# 1btn_v1.net
KiCad netlist of a schematic drawn in EAGLE
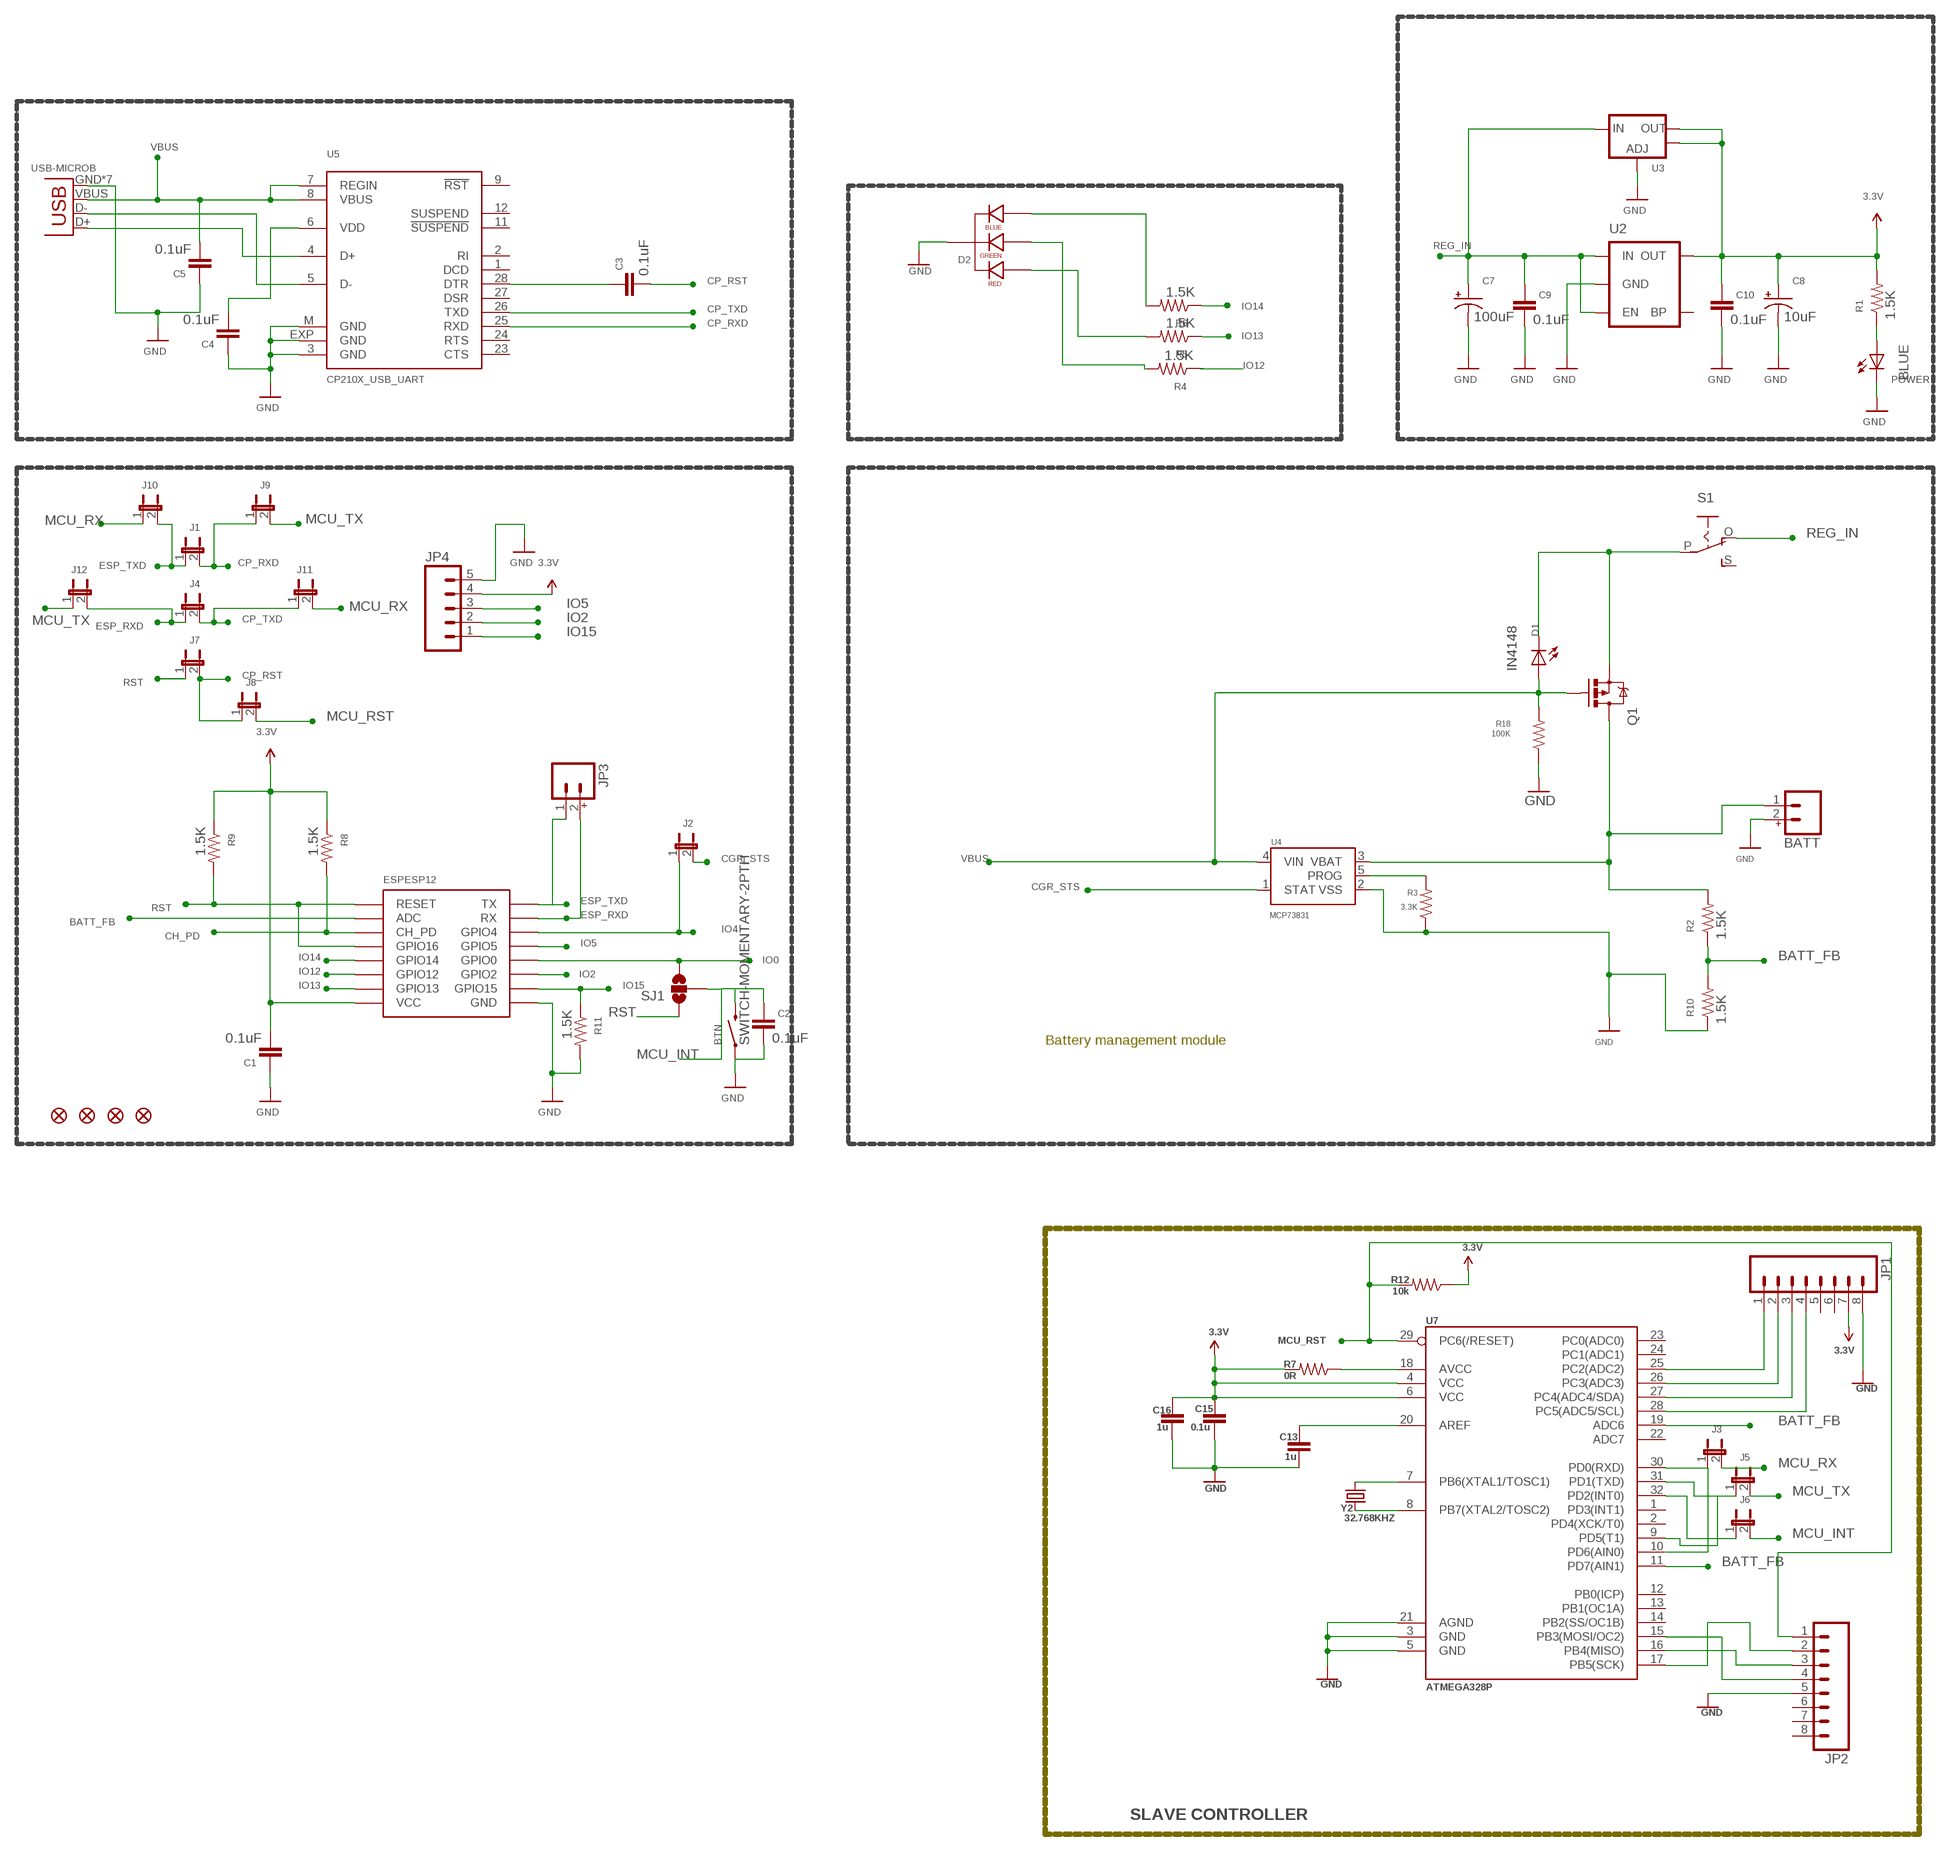
[diagram p0: schematic, sheet 1]

(export (version "E")
  (design (tool "Eeschema 10.0.6"))
  (components
    (comp (ref "BATT")
      (value "M02JST-PTH-2")
      (footprint "eagle-import:JST-2-PTH")
      (libsource (lib "eagle-import") (part "M02JST-PTH-2"))
    )
    (comp (ref "BTN")
      (value "SWITCH-MOMENTARY-2PTH")
      (footprint "eagle-import:TACTILE-PTH")
      (libsource (lib "eagle-import") (part "SWITCH-MOMENTARY-2PTH"))
    )
    (comp (ref "C1")
      (value "0.1uF")
      (footprint "eagle-import:0805")
      (libsource (lib "eagle-import") (part "SparkFun-Passives_CAP0805"))
    )
    (comp (ref "C2")
      (value "0.1uF")
      (footprint "eagle-import:0805")
      (libsource (lib "eagle-import") (part "SparkFun-Passives_CAP0805"))
    )
    (comp (ref "C3")
      (value "0.1uF")
      (footprint "eagle-import:0805")
      (libsource (lib "eagle-import") (part "SparkFun-Passives_CAP0805"))
    )
    (comp (ref "C4")
      (value "0.1uF")
      (footprint "eagle-import:0805")
      (libsource (lib "eagle-import") (part "SparkFun-Passives_CAP0805"))
    )
    (comp (ref "C5")
      (value "0.1uF")
      (footprint "eagle-import:0805")
      (libsource (lib "eagle-import") (part "SparkFun-Passives_CAP0805"))
    )
    (comp (ref "C7")
      (value "100uF")
      (footprint "eagle-import:EIA3216-KIT")
      (libsource (lib "eagle-import") (part "CAP_POL1206-KIT"))
    )
    (comp (ref "C8")
      (value "10uF")
      (footprint "eagle-import:EIA3216-KIT")
      (libsource (lib "eagle-import") (part "CAP_POL1206-KIT"))
    )
    (comp (ref "C9")
      (value "0.1uF")
      (footprint "eagle-import:0805")
      (libsource (lib "eagle-import") (part "SparkFun-Passives_CAP0805"))
    )
    (comp (ref "C10")
      (value "0.1uF")
      (footprint "eagle-import:0805")
      (libsource (lib "eagle-import") (part "SparkFun-Passives_CAP0805"))
    )
    (comp (ref "C13")
      (value "1u")
      (footprint "eagle-import:0805")
      (libsource (lib "eagle-import") (part "CAP0805"))
    )
    (comp (ref "C15")
      (value "0.1u")
      (footprint "eagle-import:0805")
      (libsource (lib "eagle-import") (part "CAP0805"))
    )
    (comp (ref "C16")
      (value "1u")
      (footprint "eagle-import:0805")
      (libsource (lib "eagle-import") (part "CAP0805"))
    )
    (comp (ref "D1")
      (value "IN4148")
      (footprint "eagle-import:LED-1206")
      (libsource (lib "eagle-import") (part "LED1206"))
    )
    (comp (ref "D2")
      (value "LED-RGB-CC-THRUCLEAR")
      (footprint "eagle-import:LED-RGB-THRU")
      (libsource (lib "eagle-import") (part "LED-RGB-CC-THRUCLEAR"))
    )
    (comp (ref "ESP")
      (value "ESP12")
      (footprint "eagle-import:ESP12")
      (libsource (lib "eagle-import") (part "ESP12"))
    )
    (comp (ref "FID1")
      (value "FIDUCIAL1X2")
      (footprint "eagle-import:FIDUCIAL-1X2")
      (libsource (lib "eagle-import") (part "FIDUCIAL1X2"))
    )
    (comp (ref "FID2")
      (value "FIDUCIAL1X2")
      (footprint "eagle-import:FIDUCIAL-1X2")
      (libsource (lib "eagle-import") (part "FIDUCIAL1X2"))
    )
    (comp (ref "FID3")
      (value "FIDUCIAL1X2")
      (footprint "eagle-import:FIDUCIAL-1X2")
      (libsource (lib "eagle-import") (part "FIDUCIAL1X2"))
    )
    (comp (ref "FID4")
      (value "FIDUCIAL1X2")
      (footprint "eagle-import:FIDUCIAL-1X2")
      (libsource (lib "eagle-import") (part "FIDUCIAL1X2"))
    )
    (comp (ref "J1")
      (value "JUMPER-2SMD-NC")
      (footprint "eagle-import:SJ_2S")
      (libsource (lib "eagle-import") (part "JUMPER-2SMD-NC"))
    )
    (comp (ref "J2")
      (value "JUMPER-2SMD-NC")
      (footprint "eagle-import:SJ_2S")
      (libsource (lib "eagle-import") (part "JUMPER-2SMD-NC"))
    )
    (comp (ref "J3")
      (value "JUMPER-2SMD-NC")
      (footprint "eagle-import:SJ_2S")
      (libsource (lib "eagle-import") (part "JUMPER-2SMD-NC"))
    )
    (comp (ref "J4")
      (value "JUMPER-2SMD-NC")
      (footprint "eagle-import:SJ_2S")
      (libsource (lib "eagle-import") (part "JUMPER-2SMD-NC"))
    )
    (comp (ref "J5")
      (value "JUMPER-2SMD-NC")
      (footprint "eagle-import:SJ_2S")
      (libsource (lib "eagle-import") (part "JUMPER-2SMD-NC"))
    )
    (comp (ref "J6")
      (value "JUMPER-2SMD-NC")
      (footprint "eagle-import:SJ_2S")
      (libsource (lib "eagle-import") (part "JUMPER-2SMD-NC"))
    )
    (comp (ref "J7")
      (value "JUMPER-2SMD-NC")
      (footprint "eagle-import:SJ_2S")
      (libsource (lib "eagle-import") (part "JUMPER-2SMD-NC"))
    )
    (comp (ref "J8")
      (value "JUMPER-2SMD-NC")
      (footprint "eagle-import:SJ_2S")
      (libsource (lib "eagle-import") (part "JUMPER-2SMD-NC"))
    )
    (comp (ref "J9")
      (value "JUMPER-2SMD-NC")
      (footprint "eagle-import:SJ_2S")
      (libsource (lib "eagle-import") (part "JUMPER-2SMD-NC"))
    )
    (comp (ref "J10")
      (value "JUMPER-2SMD-NC")
      (footprint "eagle-import:SJ_2S")
      (libsource (lib "eagle-import") (part "JUMPER-2SMD-NC"))
    )
    (comp (ref "J11")
      (value "JUMPER-2SMD-NC")
      (footprint "eagle-import:SJ_2S")
      (libsource (lib "eagle-import") (part "JUMPER-2SMD-NC"))
    )
    (comp (ref "J12")
      (value "JUMPER-2SMD-NC")
      (footprint "eagle-import:SJ_2S")
      (libsource (lib "eagle-import") (part "JUMPER-2SMD-NC"))
    )
    (comp (ref "JP1")
      (value "M08NO_SILK")
      (footprint "eagle-import:1X08_PIN1_NO_SILK")
      (libsource (lib "eagle-import") (part "M08NO_SILK"))
    )
    (comp (ref "JP2")
      (value "M08NO_SILK")
      (footprint "eagle-import:1X08_PIN1_NO_SILK")
      (libsource (lib "eagle-import") (part "M08NO_SILK"))
    )
    (comp (ref "JP3")
      (value "M02PTH")
      (footprint "eagle-import:1X02")
      (libsource (lib "eagle-import") (part "M02PTH"))
    )
    (comp (ref "JP4")
      (value "M05PTH")
      (footprint "eagle-import:1X05")
      (libsource (lib "eagle-import") (part "M05PTH"))
    )
    (comp (ref "POWER")
      (value "BLUE")
      (footprint "eagle-import:LED-0805")
      (libsource (lib "eagle-import") (part "LED"))
    )
    (comp (ref "Q1")
      (value "MOSFET-PCHANNELSMD")
      (footprint "eagle-import:SOT23-3")
      (libsource (lib "eagle-import") (part "MOSFET-PCHANNELSMD"))
    )
    (comp (ref "R1")
      (value "1.5K")
      (footprint "eagle-import:0805")
      (libsource (lib "eagle-import") (part "RESISTOR0805-RES"))
    )
    (comp (ref "R2")
      (value "1.5K")
      (footprint "eagle-import:0805")
      (libsource (lib "eagle-import") (part "RESISTOR0805-RES"))
    )
    (comp (ref "R3")
      (value "3.3K")
      (footprint "eagle-import:0805")
      (libsource (lib "eagle-import") (part "RESISTOR0805-RES"))
    )
    (comp (ref "R4")
      (value "1.5K")
      (footprint "eagle-import:0805")
      (libsource (lib "eagle-import") (part "RESISTOR0805-RES"))
    )
    (comp (ref "R5")
      (value "1.5K")
      (footprint "eagle-import:0805")
      (libsource (lib "eagle-import") (part "RESISTOR0805-RES"))
    )
    (comp (ref "R6")
      (value "1.5K")
      (footprint "eagle-import:0805")
      (libsource (lib "eagle-import") (part "RESISTOR0805-RES"))
    )
    (comp (ref "R7")
      (value "0R")
      (footprint "eagle-import:0805")
      (libsource (lib "eagle-import") (part "RESISTOR0805-RES"))
    )
    (comp (ref "R8")
      (value "1.5K")
      (footprint "eagle-import:0805")
      (libsource (lib "eagle-import") (part "RESISTOR0805-RES"))
    )
    (comp (ref "R9")
      (value "1.5K")
      (footprint "eagle-import:0805")
      (libsource (lib "eagle-import") (part "RESISTOR0805-RES"))
    )
    (comp (ref "R10")
      (value "1.5K")
      (footprint "eagle-import:0805")
      (libsource (lib "eagle-import") (part "RESISTOR0805-RES"))
    )
    (comp (ref "R11")
      (value "1.5K")
      (footprint "eagle-import:0805")
      (libsource (lib "eagle-import") (part "RESISTOR0805-RES"))
    )
    (comp (ref "R12")
      (value "10k")
      (footprint "eagle-import:0805")
      (libsource (lib "eagle-import") (part "RESISTOR0805-RES"))
    )
    (comp (ref "R18")
      (value "100K")
      (footprint "eagle-import:0805")
      (libsource (lib "eagle-import") (part "RESISTOR0805-RES"))
    )
    (comp (ref "S1")
      (value "EG1218S")
      (footprint "eagle-import:EG1218")
      (libsource (lib "eagle-import") (part "EG1218S"))
    )
    (comp (ref "SJ1")
      (value "SOLDERJUMPER_2WAYS")
      (footprint "eagle-import:SJ_3")
      (libsource (lib "eagle-import") (part "SOLDERJUMPER_2WAYS"))
    )
    (comp (ref "U2")
      (value "MIC52053.3V")
      (footprint "eagle-import:SOT23-5")
      (libsource (lib "eagle-import") (part "MIC52053.3V"))
    )
    (comp (ref "U3")
      (value "V_REG_LM1117SOT223")
      (footprint "eagle-import:SOT223")
      (libsource (lib "eagle-import") (part "V_REG_LM1117SOT223"))
    )
    (comp (ref "U4")
      (value "MCP73831")
      (footprint "eagle-import:SOT23-5")
      (libsource (lib "eagle-import") (part "MCP73831"))
    )
    (comp (ref "U5")
      (value "CP210X_USB_UART")
      (footprint "eagle-import:MLP28")
      (libsource (lib "eagle-import") (part "CP210X_USB_UART"))
    )
    (comp (ref "U7")
      (value "ATMEGA328P")
      (footprint "eagle-import:TQFP32-08")
      (libsource (lib "eagle-import") (part "ATMEGA328_SMT"))
    )
    (comp (ref "USB")
      (value "USB-MICROB")
      (footprint "eagle-import:USB-MICROB")
      (libsource (lib "eagle-import") (part "USB-MICROB"))
    )
    (comp (ref "Y2")
      (value "32.768KHZ")
      (footprint "eagle-import:TC26HEZ")
      (libsource (lib "eagle-import") (part "CRYSTALTC26H_EZ"))
    )
  )
  (nets
    (net (code "1") (name "/BATT_FB") (class "Default")
      (node (ref "ESP") (pin "ADC") (pinfunction "ADC_ADC") (pintype "bidirectional"))
      (node (ref "R10") (pin "2") (pinfunction "2_2") (pintype "passive"))
      (node (ref "R2") (pin "1") (pinfunction "1_1") (pintype "passive"))
      (node (ref "U7") (pin "11") (pinfunction "PD7(AIN1)_11") (pintype "bidirectional"))
      (node (ref "U7") (pin "19") (pinfunction "ADC6_19") (pintype "bidirectional"))
    )
    (net (code "2") (name "/CGR_STS") (class "Default")
      (node (ref "J2") (pin "2") (pinfunction "2_2") (pintype "passive"))
      (node (ref "U4") (pin "1") (pinfunction "STAT_1") (pintype "output"))
    )
    (net (code "3") (name "/CH_PD") (class "Default")
      (node (ref "ESP") (pin "CH_PD") (pinfunction "CH_PD_CH_PD") (pintype "bidirectional"))
      (node (ref "R8") (pin "2") (pinfunction "2_2") (pintype "passive"))
    )
    (net (code "4") (name "/CP_RST") (class "Default")
      (node (ref "C3") (pin "2") (pinfunction "2_2") (pintype "passive"))
      (node (ref "J7") (pin "2") (pinfunction "2_2") (pintype "passive"))
      (node (ref "J8") (pin "1") (pinfunction "1_1") (pintype "passive"))
    )
    (net (code "5") (name "/CP_RXD") (class "Default")
      (node (ref "J1") (pin "2") (pinfunction "2_2") (pintype "passive"))
      (node (ref "J9") (pin "1") (pinfunction "1_1") (pintype "passive"))
      (node (ref "U5") (pin "25") (pinfunction "RXD_25") (pintype "input"))
    )
    (net (code "6") (name "/CP_TXD") (class "Default")
      (node (ref "J11") (pin "1") (pinfunction "1_1") (pintype "passive"))
      (node (ref "J4") (pin "2") (pinfunction "2_2") (pintype "passive"))
      (node (ref "U5") (pin "26") (pinfunction "TXD_26") (pintype "output"))
    )
    (net (code "7") (name "/ESP_RXD") (class "Default")
      (node (ref "ESP") (pin "RX") (pinfunction "RX_RX") (pintype "bidirectional"))
      (node (ref "J12") (pin "2") (pinfunction "2_2") (pintype "passive"))
      (node (ref "J4") (pin "1") (pinfunction "1_1") (pintype "passive"))
      (node (ref "JP3") (pin "2") (pinfunction "2_2") (pintype "passive"))
    )
    (net (code "8") (name "/ESP_TXD") (class "Default")
      (node (ref "ESP") (pin "TX") (pinfunction "TX_TX") (pintype "bidirectional"))
      (node (ref "J1") (pin "1") (pinfunction "1_1") (pintype "passive"))
      (node (ref "J10") (pin "2") (pinfunction "2_2") (pintype "passive"))
      (node (ref "JP3") (pin "1") (pinfunction "1_1") (pintype "passive"))
    )
    (net (code "9") (name "/IO0") (class "Default")
      (node (ref "ESP") (pin "GPIO0") (pinfunction "GPIO0_GPIO0") (pintype "bidirectional"))
      (node (ref "SJ1") (pin "3") (pinfunction "3_3") (pintype "passive"))
    )
    (net (code "10") (name "/IO2") (class "Default")
      (node (ref "ESP") (pin "GPIO2") (pinfunction "GPIO2_GPIO2") (pintype "bidirectional"))
      (node (ref "JP4") (pin "2") (pinfunction "2_2") (pintype "passive"))
    )
    (net (code "11") (name "/IO4") (class "Default")
      (node (ref "ESP") (pin "GPIO4") (pinfunction "GPIO4_GPIO4") (pintype "bidirectional"))
      (node (ref "J2") (pin "1") (pinfunction "1_1") (pintype "passive"))
    )
    (net (code "12") (name "/IO5") (class "Default")
      (node (ref "ESP") (pin "GPIO5") (pinfunction "GPIO5_GPIO5") (pintype "bidirectional"))
      (node (ref "JP4") (pin "3") (pinfunction "3_3") (pintype "passive"))
    )
    (net (code "13") (name "/IO12") (class "Default")
      (node (ref "ESP") (pin "GPIO12") (pinfunction "GPIO12_GPIO12") (pintype "bidirectional"))
      (node (ref "R4") (pin "1") (pinfunction "1_1") (pintype "passive"))
    )
    (net (code "14") (name "/IO13") (class "Default")
      (node (ref "ESP") (pin "GPIO13") (pinfunction "GPIO13_GPIO13") (pintype "bidirectional"))
      (node (ref "R5") (pin "1") (pinfunction "1_1") (pintype "passive"))
    )
    (net (code "15") (name "/IO14") (class "Default")
      (node (ref "ESP") (pin "GPIO14") (pinfunction "GPIO14_GPIO14") (pintype "bidirectional"))
      (node (ref "R6") (pin "1") (pinfunction "1_1") (pintype "passive"))
    )
    (net (code "16") (name "/IO15") (class "Default")
      (node (ref "ESP") (pin "GPIO15") (pinfunction "GPIO15_GPIO15") (pintype "bidirectional"))
      (node (ref "JP4") (pin "1") (pinfunction "1_1") (pintype "passive"))
      (node (ref "R11") (pin "1") (pinfunction "1_1") (pintype "passive"))
    )
    (net (code "17") (name "/MCU_INT") (class "Default")
      (node (ref "BTN") (pin "3") (pinfunction "2_3") (pintype "passive"))
      (node (ref "C2") (pin "1") (pinfunction "1_1") (pintype "passive"))
      (node (ref "J6") (pin "2") (pinfunction "2_2") (pintype "passive"))
      (node (ref "SJ1") (pin "2") (pinfunction "2_2") (pintype "passive"))
    )
    (net (code "18") (name "/MCU_RST") (class "Default")
      (node (ref "J8") (pin "2") (pinfunction "2_2") (pintype "passive"))
      (node (ref "JP2") (pin "1") (pinfunction "1_1") (pintype "passive"))
      (node (ref "R12") (pin "2") (pinfunction "2_2") (pintype "passive"))
      (node (ref "U7") (pin "29") (pinfunction "PC6(/RESET)_29") (pintype "bidirectional"))
    )
    (net (code "19") (name "/MCU_RX") (class "Default")
      (node (ref "J10") (pin "1") (pinfunction "1_1") (pintype "passive"))
      (node (ref "J11") (pin "2") (pinfunction "2_2") (pintype "passive"))
      (node (ref "J3") (pin "2") (pinfunction "2_2") (pintype "passive"))
    )
    (net (code "20") (name "/MCU_TX") (class "Default")
      (node (ref "J12") (pin "1") (pinfunction "1_1") (pintype "passive"))
      (node (ref "J5") (pin "2") (pinfunction "2_2") (pintype "passive"))
      (node (ref "J9") (pin "2") (pinfunction "2_2") (pintype "passive"))
    )
    (net (code "21") (name "/REG_IN") (class "Default")
      (node (ref "C7") (pin "A") (pinfunction "+_A") (pintype "passive"))
      (node (ref "C9") (pin "1") (pinfunction "1_1") (pintype "passive"))
      (node (ref "S1") (pin "O") (pinfunction "O_O") (pintype "passive"))
      (node (ref "U2") (pin "1") (pinfunction "IN_1") (pintype "input"))
      (node (ref "U2") (pin "3") (pinfunction "EN_3") (pintype "input"))
      (node (ref "U3") (pin "3") (pinfunction "IN_3") (pintype "input"))
    )
    (net (code "22") (name "/RST") (class "Default")
      (node (ref "ESP") (pin "GPIO16") (pinfunction "GPIO16_GPIO16") (pintype "bidirectional"))
      (node (ref "ESP") (pin "RESET") (pinfunction "RESET_RESET") (pintype "bidirectional"))
      (node (ref "J7") (pin "1") (pinfunction "1_1") (pintype "passive"))
      (node (ref "R9") (pin "2") (pinfunction "2_2") (pintype "passive"))
      (node (ref "SJ1") (pin "1") (pinfunction "1_1") (pintype "passive"))
    )
    (net (code "23") (name "/VBUS") (class "Default")
      (node (ref "C5") (pin "2") (pinfunction "2_2") (pintype "passive"))
      (node (ref "D1") (pin "A") (pinfunction "A_A") (pintype "passive"))
      (node (ref "Q1") (pin "1") (pinfunction "G_1") (pintype "passive"))
      (node (ref "R18") (pin "2") (pinfunction "2_2") (pintype "passive"))
      (node (ref "U4") (pin "4") (pinfunction "VIN_4") (pintype "power_in"))
      (node (ref "U5") (pin "7") (pinfunction "REGIN_7") (pintype "passive"))
      (node (ref "U5") (pin "8") (pinfunction "VBUS_8") (pintype "input"))
      (node (ref "USB") (pin "VBUS") (pinfunction "VBUS_VBUS") (pintype "bidirectional"))
    )
    (net (code "24") (name "3.3V") (class "Default")
      (node (ref "C1") (pin "2") (pinfunction "2_2") (pintype "passive"))
      (node (ref "C10") (pin "1") (pinfunction "1_1") (pintype "passive"))
      (node (ref "C15") (pin "1") (pinfunction "1_1") (pintype "passive"))
      (node (ref "C16") (pin "1") (pinfunction "1_1") (pintype "passive"))
      (node (ref "C8") (pin "A") (pinfunction "+_A") (pintype "passive"))
      (node (ref "ESP") (pin "VCC") (pinfunction "VCC_VCC") (pintype "bidirectional"))
      (node (ref "JP1") (pin "7") (pinfunction "7_7") (pintype "passive"))
      (node (ref "JP4") (pin "4") (pinfunction "4_4") (pintype "passive"))
      (node (ref "R1") (pin "2") (pinfunction "2_2") (pintype "passive"))
      (node (ref "R12") (pin "1") (pinfunction "1_1") (pintype "passive"))
      (node (ref "R7") (pin "2") (pinfunction "2_2") (pintype "passive"))
      (node (ref "R8") (pin "1") (pinfunction "1_1") (pintype "passive"))
      (node (ref "R9") (pin "1") (pinfunction "1_1") (pintype "passive"))
      (node (ref "U2") (pin "5") (pinfunction "OUT_5") (pintype "passive"))
      (node (ref "U3") (pin "2") (pinfunction "OUT_2") (pintype "output"))
      (node (ref "U3") (pin "4") (pinfunction "OUT_4") (pintype "output"))
      (node (ref "U7") (pin "4") (pinfunction "VCC_4") (pintype "bidirectional"))
      (node (ref "U7") (pin "6") (pinfunction "VCC_6") (pintype "bidirectional"))
    )
    (net (code "25") (name "GND") (class "Default")
      (node (ref "BATT") (pin "2") (pinfunction "2_2") (pintype "passive"))
      (node (ref "BTN") (pin "1") (pinfunction "1_1") (pintype "passive"))
      (node (ref "C1") (pin "1") (pinfunction "1_1") (pintype "passive"))
      (node (ref "C10") (pin "2") (pinfunction "2_2") (pintype "passive"))
      (node (ref "C13") (pin "2") (pinfunction "2_2") (pintype "passive"))
      (node (ref "C15") (pin "2") (pinfunction "2_2") (pintype "passive"))
      (node (ref "C16") (pin "2") (pinfunction "2_2") (pintype "passive"))
      (node (ref "C2") (pin "2") (pinfunction "2_2") (pintype "passive"))
      (node (ref "C4") (pin "1") (pinfunction "1_1") (pintype "passive"))
      (node (ref "C5") (pin "1") (pinfunction "1_1") (pintype "passive"))
      (node (ref "C7") (pin "C") (pinfunction "-_C") (pintype "passive"))
      (node (ref "C8") (pin "C") (pinfunction "-_C") (pintype "passive"))
      (node (ref "C9") (pin "2") (pinfunction "2_2") (pintype "passive"))
      (node (ref "D2") (pin "2") (pinfunction "CATHODE_2") (pintype "bidirectional"))
      (node (ref "ESP") (pin "GND") (pinfunction "GND_GND") (pintype "bidirectional"))
      (node (ref "JP1") (pin "8") (pinfunction "8_8") (pintype "passive"))
      (node (ref "JP2") (pin "5") (pinfunction "5_5") (pintype "passive"))
      (node (ref "JP4") (pin "5") (pinfunction "5_5") (pintype "passive"))
      (node (ref "POWER") (pin "2") (pinfunction "C_2") (pintype "passive"))
      (node (ref "R10") (pin "1") (pinfunction "1_1") (pintype "passive"))
      (node (ref "R11") (pin "2") (pinfunction "2_2") (pintype "passive"))
      (node (ref "R18") (pin "1") (pinfunction "1_1") (pintype "passive"))
      (node (ref "R3") (pin "1") (pinfunction "1_1") (pintype "passive"))
      (node (ref "U2") (pin "2") (pinfunction "GND_2") (pintype "input"))
      (node (ref "U3") (pin "1") (pinfunction "ADJ_1") (pintype "input"))
      (node (ref "U4") (pin "2") (pinfunction "VSS_2") (pintype "power_in"))
      (node (ref "U5") (pin "3") (pinfunction "GND_3") (pintype "power_in"))
      (node (ref "U5") (pin "EXP") (pinfunction "GND_EXP") (pintype "power_in"))
      (node (ref "U5") (pin "M") (pinfunction "GND_M") (pintype "power_in"))
      (node (ref "U7") (pin "21") (pinfunction "AGND_21") (pintype "bidirectional"))
      (node (ref "U7") (pin "3") (pinfunction "GND_3") (pintype "bidirectional"))
      (node (ref "U7") (pin "5") (pinfunction "GND_5") (pintype "bidirectional"))
      (node (ref "USB") (pin "GND") (pinfunction "GND_GND") (pintype "bidirectional"))
      (node (ref "USB") (pin "MT1") (pinfunction "GND_MT1") (pintype "bidirectional"))
      (node (ref "USB") (pin "MT2") (pinfunction "GND_MT2") (pintype "bidirectional"))
      (node (ref "USB") (pin "MT3") (pinfunction "GND_MT3") (pintype "bidirectional"))
      (node (ref "USB") (pin "MT4") (pinfunction "GND_MT4") (pintype "bidirectional"))
      (node (ref "USB") (pin "P$1") (pinfunction "GND_P$1") (pintype "bidirectional"))
      (node (ref "USB") (pin "P$2") (pinfunction "GND_P$2") (pintype "bidirectional"))
    )
    (net (code "26") (name "Net-(D2-BLUE_CATHODE)") (class "Default")
      (node (ref "D2") (pin "4") (pinfunction "BLUE_CATHODE_4") (pintype "bidirectional"))
      (node (ref "R6") (pin "2") (pinfunction "2_2") (pintype "passive"))
    )
    (net (code "27") (name "Net-(D2-GREEN_CATHODE)") (class "Default")
      (node (ref "D2") (pin "3") (pinfunction "GREEN_CATHODE_3") (pintype "bidirectional"))
      (node (ref "R4") (pin "2") (pinfunction "2_2") (pintype "passive"))
    )
    (net (code "28") (name "Net-(D2-RED_CATHODE)") (class "Default")
      (node (ref "D2") (pin "1") (pinfunction "RED_CATHODE_1") (pintype "bidirectional"))
      (node (ref "R5") (pin "2") (pinfunction "2_2") (pintype "passive"))
    )
    (net (code "29") (name "Net-(POWER-A)") (class "Default")
      (node (ref "POWER") (pin "1") (pinfunction "A_1") (pintype "passive"))
      (node (ref "R1") (pin "1") (pinfunction "1_1") (pintype "passive"))
    )
    (net (code "30") (name "Net-(Q1-D)") (class "Default")
      (node (ref "BATT") (pin "1") (pinfunction "1_1") (pintype "passive"))
      (node (ref "Q1") (pin "3") (pinfunction "D_3") (pintype "passive"))
      (node (ref "R2") (pin "2") (pinfunction "2_2") (pintype "passive"))
      (node (ref "U4") (pin "3") (pinfunction "VBAT_3") (pintype "power_in"))
    )
    (net (code "31") (name "Net-(Q1-S)") (class "Default")
      (node (ref "D1") (pin "C") (pinfunction "C_C") (pintype "passive"))
      (node (ref "Q1") (pin "2") (pinfunction "S_2") (pintype "passive"))
      (node (ref "S1") (pin "P") (pinfunction "P_P") (pintype "passive"))
    )
    (net (code "32") (name "Net-(U4-PROG)") (class "Default")
      (node (ref "R3") (pin "2") (pinfunction "2_2") (pintype "passive"))
      (node (ref "U4") (pin "5") (pinfunction "PROG_5") (pintype "input"))
    )
    (net (code "33") (name "Net-(U5-D+)") (class "Default")
      (node (ref "U5") (pin "4") (pinfunction "D+_4") (pintype "bidirectional"))
      (node (ref "USB") (pin "D+") (pinfunction "D+_D+") (pintype "bidirectional"))
    )
    (net (code "34") (name "Net-(U5-D-)") (class "Default")
      (node (ref "U5") (pin "5") (pinfunction "D-_5") (pintype "bidirectional"))
      (node (ref "USB") (pin "D-") (pinfunction "D-_D-") (pintype "bidirectional"))
    )
    (net (code "35") (name "Net-(U5-DTR)") (class "Default")
      (node (ref "C3") (pin "1") (pinfunction "1_1") (pintype "passive"))
      (node (ref "U5") (pin "28") (pinfunction "DTR_28") (pintype "output"))
    )
    (net (code "36") (name "Net-(U5-VDD)") (class "Default")
      (node (ref "C4") (pin "2") (pinfunction "2_2") (pintype "passive"))
      (node (ref "U5") (pin "6") (pinfunction "VDD_6") (pintype "power_in"))
    )
    (net (code "37") (name "Net-(U7-AREF)") (class "Default")
      (node (ref "C13") (pin "1") (pinfunction "1_1") (pintype "passive"))
      (node (ref "U7") (pin "20") (pinfunction "AREF_20") (pintype "bidirectional"))
    )
    (net (code "38") (name "Net-(U7-AVCC)") (class "Default")
      (node (ref "R7") (pin "1") (pinfunction "1_1") (pintype "passive"))
      (node (ref "U7") (pin "18") (pinfunction "AVCC_18") (pintype "bidirectional"))
    )
    (net (code "39") (name "Net-(U7-PB3(MOSI{slash}OC2))") (class "Default")
      (node (ref "JP2") (pin "4") (pinfunction "4_4") (pintype "passive"))
      (node (ref "U7") (pin "15") (pinfunction "PB3(MOSI/OC2)_15") (pintype "bidirectional"))
    )
    (net (code "40") (name "Net-(U7-PB4(MISO))") (class "Default")
      (node (ref "JP2") (pin "3") (pinfunction "3_3") (pintype "passive"))
      (node (ref "U7") (pin "16") (pinfunction "PB4(MISO)_16") (pintype "bidirectional"))
    )
    (net (code "41") (name "Net-(U7-PB5(SCK))") (class "Default")
      (node (ref "JP2") (pin "2") (pinfunction "2_2") (pintype "passive"))
      (node (ref "U7") (pin "17") (pinfunction "PB5(SCK)_17") (pintype "bidirectional"))
    )
    (net (code "42") (name "Net-(U7-PB6(XTAL1{slash}TOSC1))") (class "Default")
      (node (ref "U7") (pin "7") (pinfunction "PB6(XTAL1/TOSC1)_7") (pintype "bidirectional"))
      (node (ref "Y2") (pin "2") (pinfunction "2_2") (pintype "passive"))
    )
    (net (code "43") (name "Net-(U7-PB7(XTAL2{slash}TOSC2))") (class "Default")
      (node (ref "U7") (pin "8") (pinfunction "PB7(XTAL2/TOSC2)_8") (pintype "bidirectional"))
      (node (ref "Y2") (pin "1") (pinfunction "1_1") (pintype "passive"))
    )
    (net (code "44") (name "Net-(U7-PC2(ADC2))") (class "Default")
      (node (ref "JP1") (pin "1") (pinfunction "1_1") (pintype "passive"))
      (node (ref "U7") (pin "25") (pinfunction "PC2(ADC2)_25") (pintype "bidirectional"))
    )
    (net (code "45") (name "Net-(U7-PC3(ADC3))") (class "Default")
      (node (ref "JP1") (pin "2") (pinfunction "2_2") (pintype "passive"))
      (node (ref "U7") (pin "26") (pinfunction "PC3(ADC3)_26") (pintype "bidirectional"))
    )
    (net (code "46") (name "Net-(U7-PC4(ADC4{slash}SDA))") (class "Default")
      (node (ref "JP1") (pin "3") (pinfunction "3_3") (pintype "passive"))
      (node (ref "U7") (pin "27") (pinfunction "PC4(ADC4/SDA)_27") (pintype "bidirectional"))
    )
    (net (code "47") (name "Net-(U7-PC5(ADC5{slash}SCL))") (class "Default")
      (node (ref "JP1") (pin "4") (pinfunction "4_4") (pintype "passive"))
      (node (ref "U7") (pin "28") (pinfunction "PC5(ADC5/SCL)_28") (pintype "bidirectional"))
    )
    (net (code "48") (name "Net-(U7-PD0(RXD))") (class "Default")
      (node (ref "J3") (pin "1") (pinfunction "1_1") (pintype "passive"))
      (node (ref "U7") (pin "10") (pinfunction "PD6(AIN0)_10") (pintype "bidirectional"))
      (node (ref "U7") (pin "30") (pinfunction "PD0(RXD)_30") (pintype "bidirectional"))
    )
    (net (code "49") (name "Net-(U7-PD1(TXD))") (class "Default")
      (node (ref "J5") (pin "1") (pinfunction "1_1") (pintype "passive"))
      (node (ref "U7") (pin "31") (pinfunction "PD1(TXD)_31") (pintype "bidirectional"))
      (node (ref "U7") (pin "9") (pinfunction "PD5(T1)_9") (pintype "bidirectional"))
    )
    (net (code "50") (name "Net-(U7-PD2(INT0))") (class "Default")
      (node (ref "J6") (pin "1") (pinfunction "1_1") (pintype "passive"))
      (node (ref "U7") (pin "32") (pinfunction "PD2(INT0)_32") (pintype "bidirectional"))
    )
    (net (code "51") (name "unconnected-(JP1-Pad5)") (class "Default")
      (node (ref "JP1") (pin "5") (pinfunction "5_5") (pintype "passive"))
    )
    (net (code "52") (name "unconnected-(JP1-Pad6)") (class "Default")
      (node (ref "JP1") (pin "6") (pinfunction "6_6") (pintype "passive"))
    )
    (net (code "53") (name "unconnected-(JP2-Pad6)") (class "Default")
      (node (ref "JP2") (pin "6") (pinfunction "6_6") (pintype "passive"))
    )
    (net (code "54") (name "unconnected-(JP2-Pad7)") (class "Default")
      (node (ref "JP2") (pin "7") (pinfunction "7_7") (pintype "passive"))
    )
    (net (code "55") (name "unconnected-(JP2-Pad8)") (class "Default")
      (node (ref "JP2") (pin "8") (pinfunction "8_8") (pintype "passive"))
    )
    (net (code "56") (name "unconnected-(S1-PadS)") (class "Default")
      (node (ref "S1") (pin "S") (pinfunction "S_S") (pintype "passive"))
    )
    (net (code "57") (name "unconnected-(U2-BP-Pad4)") (class "Default")
      (node (ref "U2") (pin "4") (pinfunction "BP_4") (pintype "input"))
    )
    (net (code "58") (name "unconnected-(U5-CTS-Pad23)") (class "Default")
      (node (ref "U5") (pin "23") (pinfunction "CTS_23") (pintype "input"))
    )
    (net (code "59") (name "unconnected-(U5-DCD-Pad1)") (class "Default")
      (node (ref "U5") (pin "1") (pinfunction "DCD_1") (pintype "input"))
    )
    (net (code "60") (name "unconnected-(U5-DSR-Pad27)") (class "Default")
      (node (ref "U5") (pin "27") (pinfunction "DSR_27") (pintype "input"))
    )
    (net (code "61") (name "unconnected-(U5-RI-Pad2)") (class "Default")
      (node (ref "U5") (pin "2") (pinfunction "RI_2") (pintype "input"))
    )
    (net (code "62") (name "unconnected-(U5-RTS-Pad24)") (class "Default")
      (node (ref "U5") (pin "24") (pinfunction "RTS_24") (pintype "output"))
    )
    (net (code "63") (name "unconnected-(U5-SUSPEND-Pad12)") (class "Default")
      (node (ref "U5") (pin "12") (pinfunction "SUSPEND_12") (pintype "output"))
    )
    (net (code "64") (name "unconnected-(U5-~{RST}-Pad9)") (class "Default")
      (node (ref "U5") (pin "9") (pinfunction "~{RST}_9") (pintype "bidirectional"))
    )
    (net (code "65") (name "unconnected-(U5-~{SUSPEND}-Pad11)") (class "Default")
      (node (ref "U5") (pin "11") (pinfunction "~{SUSPEND}_11") (pintype "output"))
    )
    (net (code "66") (name "unconnected-(U7-ADC7-Pad22)") (class "Default")
      (node (ref "U7") (pin "22") (pinfunction "ADC7_22") (pintype "bidirectional"))
    )
    (net (code "67") (name "unconnected-(U7-PB0(ICP)-Pad12)") (class "Default")
      (node (ref "U7") (pin "12") (pinfunction "PB0(ICP)_12") (pintype "bidirectional"))
    )
    (net (code "68") (name "unconnected-(U7-PB1(OC1A)-Pad13)") (class "Default")
      (node (ref "U7") (pin "13") (pinfunction "PB1(OC1A)_13") (pintype "bidirectional"))
    )
    (net (code "69") (name "unconnected-(U7-PB2(SS{slash}OC1B)-Pad14)") (class "Default")
      (node (ref "U7") (pin "14") (pinfunction "PB2(SS/OC1B)_14") (pintype "bidirectional"))
    )
    (net (code "70") (name "unconnected-(U7-PC0(ADC0)-Pad23)") (class "Default")
      (node (ref "U7") (pin "23") (pinfunction "PC0(ADC0)_23") (pintype "bidirectional"))
    )
    (net (code "71") (name "unconnected-(U7-PC1(ADC1)-Pad24)") (class "Default")
      (node (ref "U7") (pin "24") (pinfunction "PC1(ADC1)_24") (pintype "bidirectional"))
    )
    (net (code "72") (name "unconnected-(U7-PD3(INT1)-Pad1)") (class "Default")
      (node (ref "U7") (pin "1") (pinfunction "PD3(INT1)_1") (pintype "bidirectional"))
    )
    (net (code "73") (name "unconnected-(U7-PD4(XCK{slash}T0)-Pad2)") (class "Default")
      (node (ref "U7") (pin "2") (pinfunction "PD4(XCK/T0)_2") (pintype "bidirectional"))
    )
  )
)
